# CLK_src_sys_logic.net
KiCad netlist of a schematic drawn in Altium Designer
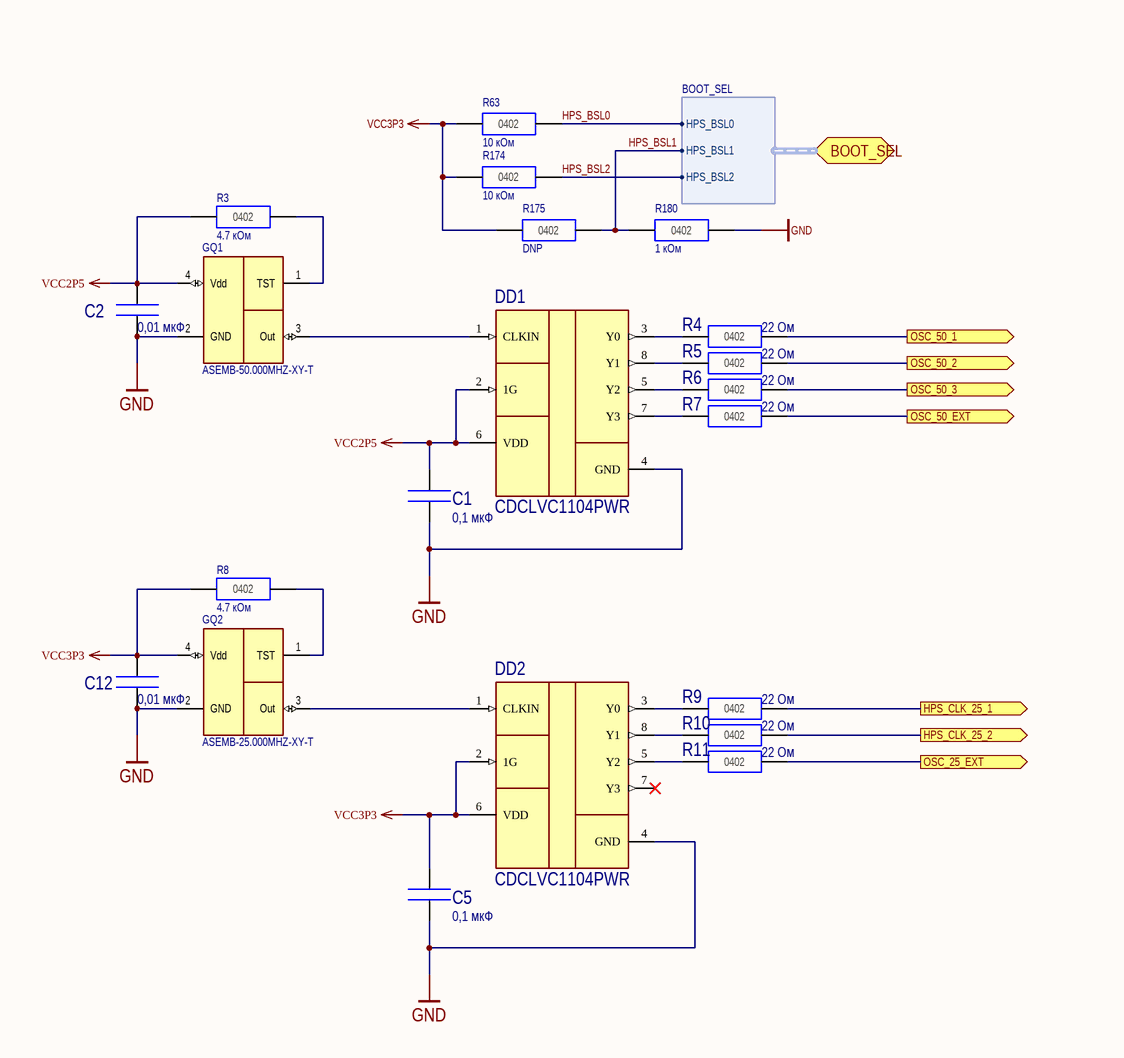
[diagram p0: CLK_src&sys_logic.SchDoc, left]
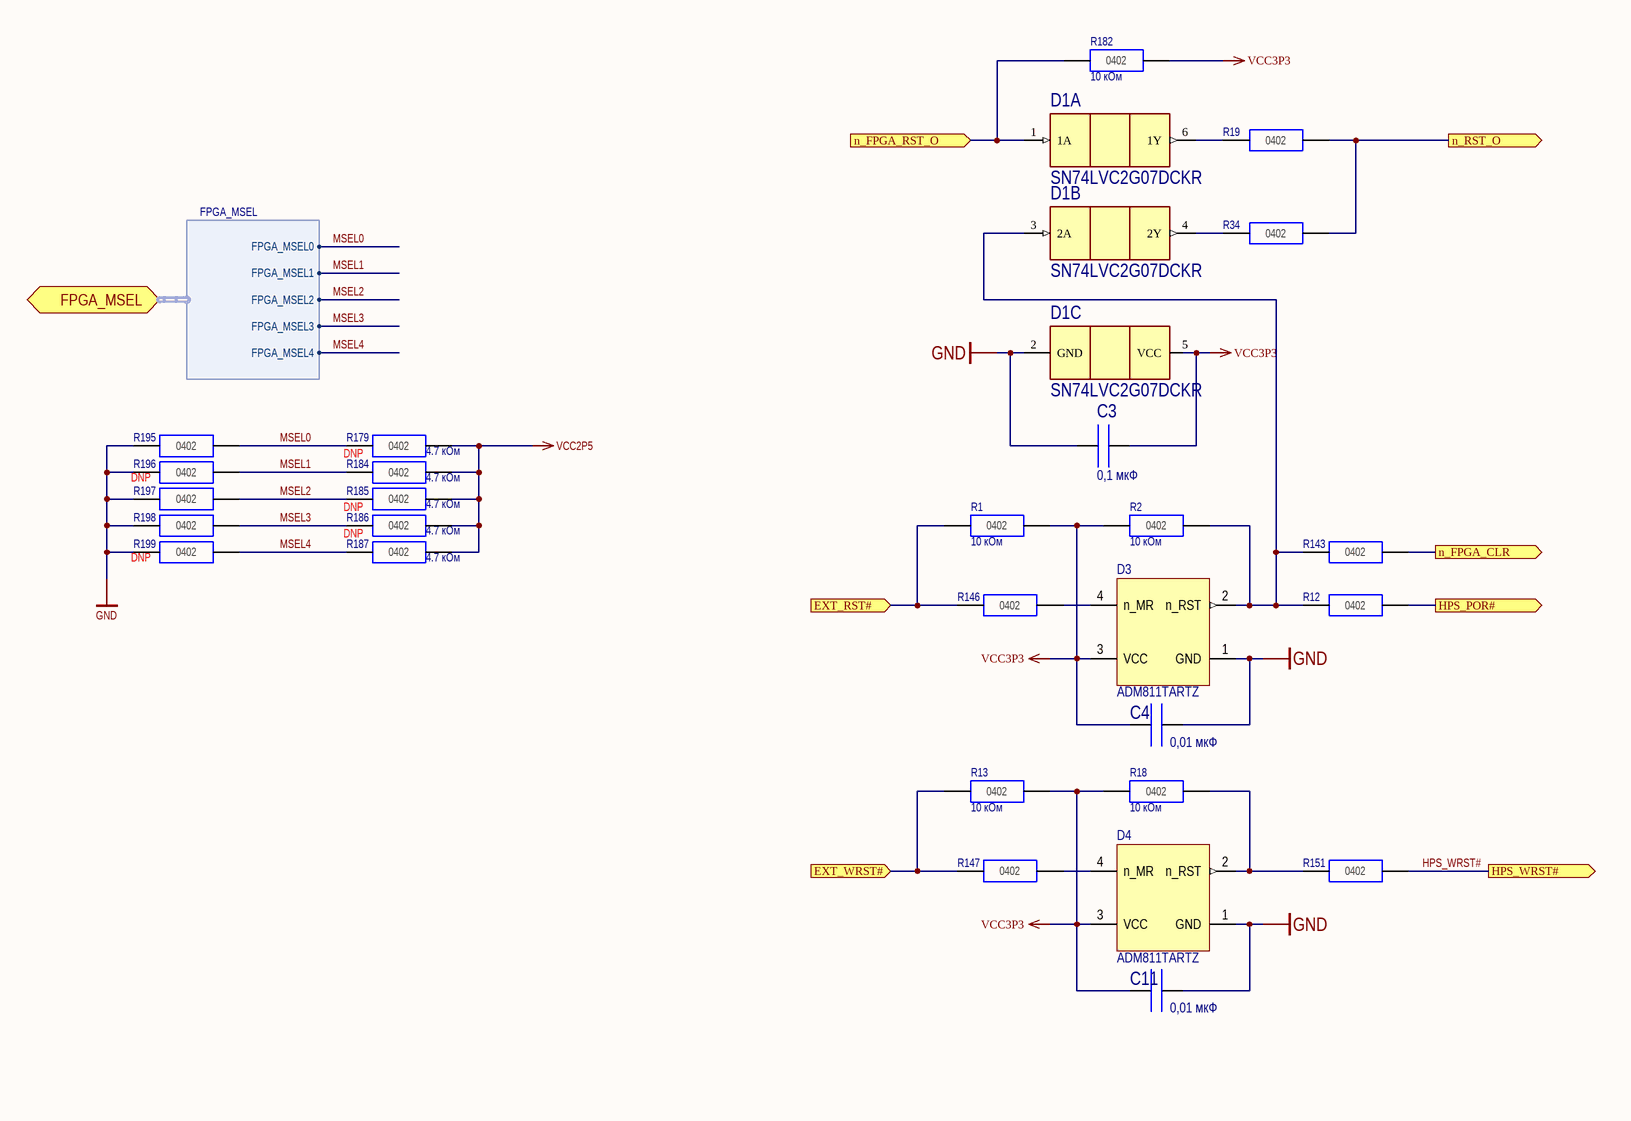
[diagram p1: CLK_src&sys_logic.SchDoc, right]

(export (version "E")
  (design (tool "Eeschema 10.0.6"))
  (components
    (comp (ref "C1")
      (value "0,1 мкФ")
      (footprint "CC0402(1005)")
      (description "Чип конденсатор керамический")
      (fields (field (name "Comment") "CC0402-X7R-0,1 мкФ-20%-10В"))
      (libsource (lib "Чип конденсаторы") (part "CC0402-X7R-#-20%-10В"))
    )
    (comp (ref "C2")
      (value "0,01 мкФ")
      (footprint "CC0402(1005)")
      (description "Чип конденсатор керамический")
      (fields (field (name "Comment") "CC0402-X7R-0,01 мкФ-10%-50В"))
      (libsource (lib "Чип конденсаторы") (part "CC0402-X7R-#-20%-10В"))
    )
    (comp (ref "C3")
      (value "0,1 мкФ")
      (footprint "CC0402(1005)")
      (description "Чип конденсатор керамический")
      (fields (field (name "Comment") "CC0402-X7R-0,1 мкФ-20%-10В"))
      (libsource (lib "Чип конденсаторы") (part "CC0402-X7R-#-20%-10В"))
    )
    (comp (ref "C4")
      (value "0,01 мкФ")
      (footprint "CC0402(1005)")
      (description "Чип конденсатор керамический")
      (fields (field (name "Comment") "CC0402-X7R-0,01 мкФ-10%-50В"))
      (libsource (lib "Чип конденсаторы") (part "CC0402-X7R-#-20%-10В"))
    )
    (comp (ref "C5")
      (value "0,1 мкФ")
      (footprint "CC0402(1005)")
      (description "Чип конденсатор керамический")
      (fields (field (name "Comment") "CC0402-X7R-0,1 мкФ-20%-10В"))
      (libsource (lib "Чип конденсаторы") (part "CC0402-X7R-#-20%-10В"))
    )
    (comp (ref "C11")
      (value "0,01 мкФ")
      (footprint "CC0402(1005)")
      (description "Чип конденсатор керамический")
      (fields (field (name "Comment") "CC0402-X7R-0,01 мкФ-10%-50В"))
      (libsource (lib "Чип конденсаторы") (part "CC0402-X7R-#-20%-10В"))
    )
    (comp (ref "C12")
      (value "0,01 мкФ")
      (footprint "CC0402(1005)")
      (description "Чип конденсатор керамический")
      (fields (field (name "Comment") "CC0402-X7R-0,01 мкФ-10%-50В"))
      (libsource (lib "Чип конденсаторы") (part "CC0402-X7R-#-20%-10В"))
    )
    (comp (ref "D1")
      (value "SN74LVC2G07DCKR")
      (footprint "DCKR")
      (description "Dual Buffer and Driver With Open-Drain Outputs")
      (libsource (lib "SD_IC") (part "IC_TI_SN74LVC2G07"))
    )
    (comp (ref "D3")
      (value "ADM811TARTZ")
      (footprint "SOT-143")
      (description "Microprocessor Supervisory Circuit in 3-Pin SOT-23")
      (fields (field (name "PUBLISHER") "Altium Limited"))
      (libsource (lib "SD_IC") (part "IC_AD_ADM811TARTZ"))
    )
    (comp (ref "D4")
      (value "ADM811TARTZ")
      (footprint "SOT-143")
      (description "Microprocessor Supervisory Circuit in 3-Pin SOT-23")
      (fields (field (name "PUBLISHER") "Altium Limited"))
      (libsource (lib "SD_IC") (part "IC_AD_ADM811TARTZ"))
    )
    (comp (ref "DD1")
      (value "CDCLVC1104PWR")
      (footprint "TSSOP-8")
      (description "High-Performance  Clock Buffer 1:4")
      (libsource (lib "Микросхемы") (part "CDCLVC1104PWR"))
    )
    (comp (ref "DD2")
      (value "CDCLVC1104PWR")
      (footprint "TSSOP-8")
      (description "High-Performance  Clock Buffer 1:4")
      (libsource (lib "Микросхемы") (part "CDCLVC1104PWR"))
    )
    (comp (ref "GQ1")
      (value "ASEMB-50.000MHZ-XY-T")
      (footprint "DFN210P320X100-4N")
      (description "Dual High Side Switch With OC_DET 500mA/CH")
      (fields (field (name "MANUFACTURER PART NO.") "ASEMB-50.000MHZ-XY-T"))
      (libsource (lib "SD_IC") (part "OSC-ABRCN-ASE3"))
    )
    (comp (ref "GQ2")
      (value "ASEMB-25.000MHZ-XY-T")
      (footprint "DFN210P320X100-4N")
      (description "Dual High Side Switch With OC_DET 500mA/CH")
      (fields (field (name "MANUFACTURER PART NO.") "ASEMB-25.000MHZ-XY-T"))
      (libsource (lib "SD_IC") (part "OSC-ABRCN-ASE3"))
    )
    (comp (ref "R1")
      (value "10 кОм")
      (footprint "CR0402(1005)")
      (description "Чип резистор")
      (fields (field (name "TOLERANCE") "5%") (field (name "Comment") "CR0402-10 кОм-±5%"))
      (libsource (lib "Резисторы") (part "CR0402-#-±5%"))
    )
    (comp (ref "R2")
      (value "10 кОм")
      (footprint "CR0402(1005)")
      (description "Чип резистор")
      (fields (field (name "TOLERANCE") "5%") (field (name "Comment") "CR0402-10 кОм-±5%"))
      (libsource (lib "Резисторы") (part "CR0402-#-±5%"))
    )
    (comp (ref "R3")
      (value "4.7 кОм")
      (footprint "CR0402(1005)")
      (description "Чип резистор")
      (fields (field (name "TOLERANCE") "5%") (field (name "Comment") "CR0402-4.7 кОм-±5%"))
      (libsource (lib "Резисторы") (part "CR0402-#-±5%"))
    )
    (comp (ref "R4")
      (value "22 Ом")
      (footprint "CR0402(1005)")
      (description "Чип резистор")
      (fields (field (name "TOLERANCE") "5%") (field (name "Comment") "CR0402-22 Ом-±5%"))
      (libsource (lib "Чип резисторы") (part "CR0402-#-±5%"))
    )
    (comp (ref "R5")
      (value "22 Ом")
      (footprint "CR0402(1005)")
      (description "Чип резистор")
      (fields (field (name "TOLERANCE") "5%") (field (name "Comment") "CR0402-22 Ом-±5%"))
      (libsource (lib "Чип резисторы") (part "CR0402-#-±5%"))
    )
    (comp (ref "R6")
      (value "22 Ом")
      (footprint "CR0402(1005)")
      (description "Чип резистор")
      (fields (field (name "TOLERANCE") "5%") (field (name "Comment") "CR0402-22 Ом-±5%"))
      (libsource (lib "Чип резисторы") (part "CR0402-#-±5%"))
    )
    (comp (ref "R7")
      (value "22 Ом")
      (footprint "CR0402(1005)")
      (description "Чип резистор")
      (fields (field (name "TOLERANCE") "5%") (field (name "Comment") "CR0402-22 Ом-±5%"))
      (libsource (lib "Чип резисторы") (part "CR0402-#-±5%"))
    )
    (comp (ref "R8")
      (value "4.7 кОм")
      (footprint "CR0402(1005)")
      (description "Чип резистор")
      (fields (field (name "TOLERANCE") "5%") (field (name "Comment") "CR0402-4.7 кОм-±5%"))
      (libsource (lib "Резисторы") (part "CR0402-#-±5%"))
    )
    (comp (ref "R9")
      (value "22 Ом")
      (footprint "CR0402(1005)")
      (description "Чип резистор")
      (fields (field (name "TOLERANCE") "5%") (field (name "Comment") "CR0402-22 Ом-±5%"))
      (libsource (lib "Чип резисторы") (part "CR0402-#-±5%"))
    )
    (comp (ref "R10")
      (value "22 Ом")
      (footprint "CR0402(1005)")
      (description "Чип резистор")
      (fields (field (name "TOLERANCE") "5%") (field (name "Comment") "CR0402-22 Ом-±5%"))
      (libsource (lib "Чип резисторы") (part "CR0402-#-±5%"))
    )
    (comp (ref "R11")
      (value "22 Ом")
      (footprint "CR0402(1005)")
      (description "Чип резистор")
      (fields (field (name "TOLERANCE") "5%") (field (name "Comment") "CR0402-22 Ом-±5%"))
      (libsource (lib "Чип резисторы") (part "CR0402-#-±5%"))
    )
    (comp (ref "R12")
      (value "CR0402-0 Ом-±5%")
      (footprint "CR0402(1005)")
      (description "Чип резистор")
      (fields (field (name "TOLERANCE") "5%"))
      (libsource (lib "Резисторы") (part "CR0402-#-±5%"))
    )
    (comp (ref "R13")
      (value "10 кОм")
      (footprint "CR0402(1005)")
      (description "Чип резистор")
      (fields (field (name "TOLERANCE") "5%") (field (name "Comment") "CR0402-10 кОм-±5%"))
      (libsource (lib "Резисторы") (part "CR0402-#-±5%"))
    )
    (comp (ref "R18")
      (value "10 кОм")
      (footprint "CR0402(1005)")
      (description "Чип резистор")
      (fields (field (name "TOLERANCE") "5%") (field (name "Comment") "CR0402-10 кОм-±5%"))
      (libsource (lib "Резисторы") (part "CR0402-#-±5%"))
    )
    (comp (ref "R19")
      (value "CR0402-0 Ом-±5%")
      (footprint "CR0402(1005)")
      (description "Чип резистор")
      (fields (field (name "TOLERANCE") "5%"))
      (libsource (lib "Резисторы") (part "CR0402-#-±5%"))
    )
    (comp (ref "R34")
      (value "CR0402-0 Ом-±5%")
      (footprint "CR0402(1005)")
      (description "Чип резистор")
      (fields (field (name "TOLERANCE") "5%"))
      (libsource (lib "Резисторы") (part "CR0402-#-±5%"))
    )
    (comp (ref "R63")
      (value "10 кОм")
      (footprint "CR0402(1005)")
      (description "Чип резистор")
      (fields (field (name "TOLERANCE") "5%") (field (name "Comment") "CR0402-10 кОм-±5%"))
      (libsource (lib "Резисторы") (part "CR0402-#-±5%"))
    )
    (comp (ref "R143")
      (value "CR0402-0 Ом-±5%")
      (footprint "CR0402(1005)")
      (description "Чип резистор")
      (fields (field (name "TOLERANCE") "5%"))
      (libsource (lib "Резисторы") (part "CR0402-#-±5%"))
    )
    (comp (ref "R146")
      (value "CR0402-0 Ом-±5%")
      (footprint "CR0402(1005)")
      (description "Чип резистор")
      (fields (field (name "TOLERANCE") "5%"))
      (libsource (lib "Резисторы") (part "CR0402-#-±5%"))
    )
    (comp (ref "R147")
      (value "CR0402-0 Ом-±5%")
      (footprint "CR0402(1005)")
      (description "Чип резистор")
      (fields (field (name "TOLERANCE") "5%"))
      (libsource (lib "Резисторы") (part "CR0402-#-±5%"))
    )
    (comp (ref "R151")
      (value "CR0402-0 Ом-±5%")
      (footprint "CR0402(1005)")
      (description "Чип резистор")
      (fields (field (name "TOLERANCE") "5%"))
      (libsource (lib "Резисторы") (part "CR0402-#-±5%"))
    )
    (comp (ref "R174")
      (value "10 кОм")
      (footprint "CR0402(1005)")
      (description "Чип резистор")
      (fields (field (name "TOLERANCE") "5%") (field (name "Comment") "CR0402-10 кОм-±5%"))
      (libsource (lib "Резисторы") (part "CR0402-#-±5%"))
    )
    (comp (ref "R175")
      (value "DNP")
      (footprint "CR0402(1005)")
      (description "Чип резистор")
      (fields (field (name "TOLERANCE") "5%") (field (name "Comment") "CR0402-DNP-±5%"))
      (libsource (lib "Резисторы") (part "CR0402-#-±5%"))
    )
    (comp (ref "R179")
      (value "4.7 кОм")
      (footprint "CR0402(1005)")
      (description "Чип резистор")
      (fields
        (field (name "TOLERANCE") "5%")
        (field (name "PLACE") "DNP")
        (field (name "Comment") "CR0402-4.7 кОм-±5%")
      )
      (libsource (lib "Резисторы") (part "CR0402-#-±5%"))
    )
    (comp (ref "R180")
      (value "1 кОм")
      (footprint "CR0402(1005)")
      (description "Чип резистор")
      (fields (field (name "TOLERANCE") "5%") (field (name "Comment") "CR0402-1 кОм-±5%"))
      (libsource (lib "Резисторы") (part "CR0402-#-±5%"))
    )
    (comp (ref "R182")
      (value "10 кОм")
      (footprint "CR0402(1005)")
      (description "Чип резистор")
      (fields (field (name "TOLERANCE") "5%") (field (name "Comment") "CR0402-10 кОм-±5%"))
      (libsource (lib "Резисторы") (part "CR0402-#-±5%"))
    )
    (comp (ref "R184")
      (value "4.7 кОм")
      (footprint "CR0402(1005)")
      (description "Чип резистор")
      (fields (field (name "TOLERANCE") "5%") (field (name "Comment") "CR0402-4.7 кОм-±5%"))
      (libsource (lib "Резисторы") (part "CR0402-#-±5%"))
    )
    (comp (ref "R185")
      (value "4.7 кОм")
      (footprint "CR0402(1005)")
      (description "Чип резистор")
      (fields
        (field (name "TOLERANCE") "5%")
        (field (name "PLACE") "DNP")
        (field (name "Comment") "CR0402-4.7 кОм-±5%")
      )
      (libsource (lib "Резисторы") (part "CR0402-#-±5%"))
    )
    (comp (ref "R186")
      (value "4.7 кОм")
      (footprint "CR0402(1005)")
      (description "Чип резистор")
      (fields
        (field (name "TOLERANCE") "5%")
        (field (name "PLACE") "DNP")
        (field (name "Comment") "CR0402-4.7 кОм-±5%")
      )
      (libsource (lib "Резисторы") (part "CR0402-#-±5%"))
    )
    (comp (ref "R187")
      (value "4.7 кОм")
      (footprint "CR0402(1005)")
      (description "Чип резистор")
      (fields (field (name "TOLERANCE") "5%") (field (name "Comment") "CR0402-4.7 кОм-±5%"))
      (libsource (lib "Резисторы") (part "CR0402-#-±5%"))
    )
    (comp (ref "R195")
      (value "CR0402-0 Ом-±5%")
      (footprint "CR0402(1005)")
      (description "Чип резистор")
      (fields (field (name "TOLERANCE") "5%"))
      (libsource (lib "Резисторы") (part "CR0402-#-±5%"))
    )
    (comp (ref "R196")
      (value "CR0402-0 Ом-±5%")
      (footprint "CR0402(1005)")
      (description "Чип резистор")
      (fields (field (name "TOLERANCE") "5%") (field (name "PLACE") "DNP"))
      (libsource (lib "Резисторы") (part "CR0402-#-±5%"))
    )
    (comp (ref "R197")
      (value "CR0402-0 Ом-±5%")
      (footprint "CR0402(1005)")
      (description "Чип резистор")
      (fields (field (name "TOLERANCE") "5%"))
      (libsource (lib "Резисторы") (part "CR0402-#-±5%"))
    )
    (comp (ref "R198")
      (value "CR0402-0 Ом-±5%")
      (footprint "CR0402(1005)")
      (description "Чип резистор")
      (fields (field (name "TOLERANCE") "5%"))
      (libsource (lib "Резисторы") (part "CR0402-#-±5%"))
    )
    (comp (ref "R199")
      (value "CR0402-0 Ом-±5%")
      (footprint "CR0402(1005)")
      (description "Чип резистор")
      (fields (field (name "TOLERANCE") "5%") (field (name "PLACE") "DNP"))
      (libsource (lib "Резисторы") (part "CR0402-#-±5%"))
    )
  )
  (nets
    (net (code "3") (name "/EXT_RST#") (class "Default")
      (node (ref "R1") (pin "1") (pinfunction "+_1") (pintype "passive"))
      (node (ref "R146") (pin "1") (pinfunction "+_1") (pintype "passive"))
    )
    (net (code "4") (name "/EXT_WRST#") (class "Default")
      (node (ref "R13") (pin "1") (pinfunction "+_1") (pintype "passive"))
      (node (ref "R147") (pin "1") (pinfunction "+_1") (pintype "passive"))
    )
    (net (code "5") (name "/HPS_BSL0") (class "Default")
      (node (ref "R63") (pin "2") (pinfunction "-_2") (pintype "passive"))
    )
    (net (code "6") (name "/HPS_BSL1") (class "Default")
      (node (ref "R175") (pin "2") (pinfunction "-_2") (pintype "passive"))
      (node (ref "R180") (pin "1") (pinfunction "+_1") (pintype "passive"))
    )
    (net (code "7") (name "/HPS_BSL2") (class "Default")
      (node (ref "R174") (pin "2") (pinfunction "-_2") (pintype "passive"))
    )
    (net (code "8") (name "/HPS_CLK_25_1") (class "Default")
      (node (ref "R9") (pin "2") (pinfunction "-_2") (pintype "passive"))
    )
    (net (code "9") (name "/HPS_CLK_25_2") (class "Default")
      (node (ref "R10") (pin "2") (pinfunction "-_2") (pintype "passive"))
    )
    (net (code "10") (name "/HPS_POR#") (class "Default")
      (node (ref "R12") (pin "2") (pinfunction "-_2") (pintype "passive"))
    )
    (net (code "11") (name "/HPS_WRST#") (class "Default")
      (node (ref "R151") (pin "2") (pinfunction "-_2") (pintype "passive"))
    )
    (net (code "12") (name "/MSEL0") (class "Default")
      (node (ref "R179") (pin "1") (pinfunction "+_1") (pintype "passive"))
      (node (ref "R195") (pin "2") (pinfunction "-_2") (pintype "passive"))
    )
    (net (code "13") (name "/MSEL1") (class "Default")
      (node (ref "R184") (pin "1") (pinfunction "+_1") (pintype "passive"))
      (node (ref "R196") (pin "2") (pinfunction "-_2") (pintype "passive"))
    )
    (net (code "14") (name "/MSEL2") (class "Default")
      (node (ref "R185") (pin "1") (pinfunction "+_1") (pintype "passive"))
      (node (ref "R197") (pin "2") (pinfunction "-_2") (pintype "passive"))
    )
    (net (code "15") (name "/MSEL3") (class "Default")
      (node (ref "R186") (pin "1") (pinfunction "+_1") (pintype "passive"))
      (node (ref "R198") (pin "2") (pinfunction "-_2") (pintype "passive"))
    )
    (net (code "16") (name "/MSEL4") (class "Default")
      (node (ref "R187") (pin "1") (pinfunction "+_1") (pintype "passive"))
      (node (ref "R199") (pin "2") (pinfunction "-_2") (pintype "passive"))
    )
    (net (code "17") (name "/OSC_25_EXT") (class "Default")
      (node (ref "R11") (pin "2") (pinfunction "-_2") (pintype "passive"))
    )
    (net (code "18") (name "/OSC_50_1") (class "Default")
      (node (ref "R4") (pin "2") (pinfunction "-_2") (pintype "passive"))
    )
    (net (code "19") (name "/OSC_50_2") (class "Default")
      (node (ref "R5") (pin "2") (pinfunction "-_2") (pintype "passive"))
    )
    (net (code "20") (name "/OSC_50_3") (class "Default")
      (node (ref "R6") (pin "2") (pinfunction "-_2") (pintype "passive"))
    )
    (net (code "21") (name "/OSC_50_EXT") (class "Default")
      (node (ref "R7") (pin "2") (pinfunction "-_2") (pintype "passive"))
    )
    (net (code "22") (name "/n_FPGA_CLR") (class "Default")
      (node (ref "R143") (pin "2") (pinfunction "-_2") (pintype "passive"))
    )
    (net (code "23") (name "/n_FPGA_RST_O") (class "Default")
      (node (ref "D1") (pin "1") (pinfunction "1A_1") (pintype "input"))
      (node (ref "R182") (pin "1") (pinfunction "+_1") (pintype "passive"))
    )
    (net (code "24") (name "/n_RST_O") (class "Default")
      (node (ref "R19") (pin "2") (pinfunction "-_2") (pintype "passive"))
      (node (ref "R34") (pin "2") (pinfunction "-_2") (pintype "passive"))
    )
    (net (code "27") (name "GND") (class "Default")
      (node (ref "C1") (pin "2") (pinfunction "-_2") (pintype "passive"))
      (node (ref "C11") (pin "1") (pinfunction "+_1") (pintype "passive"))
      (node (ref "C12") (pin "1") (pinfunction "+_1") (pintype "passive"))
      (node (ref "C2") (pin "1") (pinfunction "+_1") (pintype "passive"))
      (node (ref "C3") (pin "1") (pinfunction "+_1") (pintype "passive"))
      (node (ref "C4") (pin "1") (pinfunction "+_1") (pintype "passive"))
      (node (ref "C5") (pin "2") (pinfunction "-_2") (pintype "passive"))
      (node (ref "D1") (pin "2") (pinfunction "GND_2") (pintype "power_in"))
      (node (ref "D3") (pin "1") (pinfunction "GND_1") (pintype "power_in"))
      (node (ref "D4") (pin "1") (pinfunction "GND_1") (pintype "power_in"))
      (node (ref "DD1") (pin "4") (pinfunction "GND_4") (pintype "power_in"))
      (node (ref "DD2") (pin "4") (pinfunction "GND_4") (pintype "power_in"))
      (node (ref "GQ1") (pin "2") (pinfunction "GND_2") (pintype "power_in"))
      (node (ref "GQ2") (pin "2") (pinfunction "GND_2") (pintype "power_in"))
      (node (ref "R180") (pin "2") (pinfunction "-_2") (pintype "passive"))
      (node (ref "R195") (pin "1") (pinfunction "+_1") (pintype "passive"))
      (node (ref "R196") (pin "1") (pinfunction "+_1") (pintype "passive"))
      (node (ref "R197") (pin "1") (pinfunction "+_1") (pintype "passive"))
      (node (ref "R198") (pin "1") (pinfunction "+_1") (pintype "passive"))
      (node (ref "R199") (pin "1") (pinfunction "+_1") (pintype "passive"))
    )
    (net (code "28") (name "Net-(D1A-1Y)") (class "Default")
      (node (ref "D1") (pin "6") (pinfunction "1Y_6") (pintype "output"))
      (node (ref "R19") (pin "1") (pinfunction "+_1") (pintype "passive"))
    )
    (net (code "29") (name "Net-(D1B-2A)") (class "Default")
      (node (ref "D1") (pin "3") (pinfunction "2A_3") (pintype "input"))
      (node (ref "D3") (pin "2") (pinfunction "n_RST_2") (pintype "output"))
      (node (ref "R12") (pin "1") (pinfunction "+_1") (pintype "passive"))
      (node (ref "R143") (pin "1") (pinfunction "+_1") (pintype "passive"))
      (node (ref "R2") (pin "2") (pinfunction "-_2") (pintype "passive"))
    )
    (net (code "30") (name "Net-(D1B-2Y)") (class "Default")
      (node (ref "D1") (pin "4") (pinfunction "2Y_4") (pintype "output"))
      (node (ref "R34") (pin "1") (pinfunction "+_1") (pintype "passive"))
    )
    (net (code "31") (name "Net-(D3-n_MR)") (class "Default")
      (node (ref "D3") (pin "4") (pinfunction "n_MR_4") (pintype "power_in"))
      (node (ref "R146") (pin "2") (pinfunction "-_2") (pintype "passive"))
    )
    (net (code "32") (name "Net-(D4-n_MR)") (class "Default")
      (node (ref "D4") (pin "4") (pinfunction "n_MR_4") (pintype "power_in"))
      (node (ref "R147") (pin "2") (pinfunction "-_2") (pintype "passive"))
    )
    (net (code "33") (name "Net-(D4-n_RST)") (class "Default")
      (node (ref "D4") (pin "2") (pinfunction "n_RST_2") (pintype "output"))
      (node (ref "R151") (pin "1") (pinfunction "+_1") (pintype "passive"))
      (node (ref "R18") (pin "2") (pinfunction "-_2") (pintype "passive"))
    )
    (net (code "34") (name "Net-(DD1-CLKIN)") (class "Default")
      (node (ref "DD1") (pin "1") (pinfunction "CLKIN_1") (pintype "input"))
      (node (ref "GQ1") (pin "3") (pinfunction "Out_3") (pintype "bidirectional"))
    )
    (net (code "35") (name "Net-(DD1-Y0)") (class "Default")
      (node (ref "DD1") (pin "3") (pinfunction "Y0_3") (pintype "output"))
      (node (ref "R4") (pin "1") (pinfunction "+_1") (pintype "passive"))
    )
    (net (code "36") (name "Net-(DD1-Y1)") (class "Default")
      (node (ref "DD1") (pin "8") (pinfunction "Y1_8") (pintype "output"))
      (node (ref "R5") (pin "1") (pinfunction "+_1") (pintype "passive"))
    )
    (net (code "37") (name "Net-(DD1-Y2)") (class "Default")
      (node (ref "DD1") (pin "5") (pinfunction "Y2_5") (pintype "output"))
      (node (ref "R6") (pin "1") (pinfunction "+_1") (pintype "passive"))
    )
    (net (code "38") (name "Net-(DD1-Y3)") (class "Default")
      (node (ref "DD1") (pin "7") (pinfunction "Y3_7") (pintype "output"))
      (node (ref "R7") (pin "1") (pinfunction "+_1") (pintype "passive"))
    )
    (net (code "39") (name "Net-(DD2-CLKIN)") (class "Default")
      (node (ref "DD2") (pin "1") (pinfunction "CLKIN_1") (pintype "input"))
      (node (ref "GQ2") (pin "3") (pinfunction "Out_3") (pintype "bidirectional"))
    )
    (net (code "40") (name "Net-(DD2-Y0)") (class "Default")
      (node (ref "DD2") (pin "3") (pinfunction "Y0_3") (pintype "output"))
      (node (ref "R9") (pin "1") (pinfunction "+_1") (pintype "passive"))
    )
    (net (code "41") (name "Net-(DD2-Y1)") (class "Default")
      (node (ref "DD2") (pin "8") (pinfunction "Y1_8") (pintype "output"))
      (node (ref "R10") (pin "1") (pinfunction "+_1") (pintype "passive"))
    )
    (net (code "42") (name "Net-(DD2-Y2)") (class "Default")
      (node (ref "DD2") (pin "5") (pinfunction "Y2_5") (pintype "output"))
      (node (ref "R11") (pin "1") (pinfunction "+_1") (pintype "passive"))
    )
    (net (code "43") (name "Net-(GQ1-TST)") (class "Default")
      (node (ref "GQ1") (pin "1") (pinfunction "TST_1") (pintype "power_in"))
      (node (ref "R3") (pin "2") (pinfunction "-_2") (pintype "passive"))
    )
    (net (code "44") (name "Net-(GQ2-TST)") (class "Default")
      (node (ref "GQ2") (pin "1") (pinfunction "TST_1") (pintype "power_in"))
      (node (ref "R8") (pin "2") (pinfunction "-_2") (pintype "passive"))
    )
    (net (code "45") (name "VCC2P5") (class "Default")
      (node (ref "C1") (pin "1") (pinfunction "+_1") (pintype "passive"))
      (node (ref "C2") (pin "2") (pinfunction "-_2") (pintype "passive"))
      (node (ref "DD1") (pin "2") (pinfunction "1G_2") (pintype "input"))
      (node (ref "DD1") (pin "6") (pinfunction "VDD_6") (pintype "power_in"))
      (node (ref "GQ1") (pin "4") (pinfunction "Vdd_4") (pintype "bidirectional"))
      (node (ref "R179") (pin "2") (pinfunction "-_2") (pintype "passive"))
      (node (ref "R184") (pin "2") (pinfunction "-_2") (pintype "passive"))
      (node (ref "R185") (pin "2") (pinfunction "-_2") (pintype "passive"))
      (node (ref "R186") (pin "2") (pinfunction "-_2") (pintype "passive"))
      (node (ref "R187") (pin "2") (pinfunction "-_2") (pintype "passive"))
      (node (ref "R3") (pin "1") (pinfunction "+_1") (pintype "passive"))
    )
    (net (code "46") (name "VCC3P3") (class "Default")
      (node (ref "C11") (pin "2") (pinfunction "-_2") (pintype "passive"))
      (node (ref "C12") (pin "2") (pinfunction "-_2") (pintype "passive"))
      (node (ref "C3") (pin "2") (pinfunction "-_2") (pintype "passive"))
      (node (ref "C4") (pin "2") (pinfunction "-_2") (pintype "passive"))
      (node (ref "C5") (pin "1") (pinfunction "+_1") (pintype "passive"))
      (node (ref "D1") (pin "5") (pinfunction "VCC_5") (pintype "power_in"))
      (node (ref "D3") (pin "3") (pinfunction "VCC_3") (pintype "power_in"))
      (node (ref "D4") (pin "3") (pinfunction "VCC_3") (pintype "power_in"))
      (node (ref "DD2") (pin "2") (pinfunction "1G_2") (pintype "input"))
      (node (ref "DD2") (pin "6") (pinfunction "VDD_6") (pintype "power_in"))
      (node (ref "GQ2") (pin "4") (pinfunction "Vdd_4") (pintype "bidirectional"))
      (node (ref "R1") (pin "2") (pinfunction "-_2") (pintype "passive"))
      (node (ref "R13") (pin "2") (pinfunction "-_2") (pintype "passive"))
      (node (ref "R174") (pin "1") (pinfunction "+_1") (pintype "passive"))
      (node (ref "R175") (pin "1") (pinfunction "+_1") (pintype "passive"))
      (node (ref "R18") (pin "1") (pinfunction "+_1") (pintype "passive"))
      (node (ref "R182") (pin "2") (pinfunction "-_2") (pintype "passive"))
      (node (ref "R2") (pin "1") (pinfunction "+_1") (pintype "passive"))
      (node (ref "R63") (pin "1") (pinfunction "+_1") (pintype "passive"))
      (node (ref "R8") (pin "1") (pinfunction "+_1") (pintype "passive"))
    )
    (net (code "47") (name "unconnected-(DD2-Y3-Pad7)") (class "Default")
      (node (ref "DD2") (pin "7") (pinfunction "Y3_7") (pintype "output+no_connect"))
    )
  )
)
